# 03_MCU.net
KiCad netlist of a schematic drawn in Altium Designer
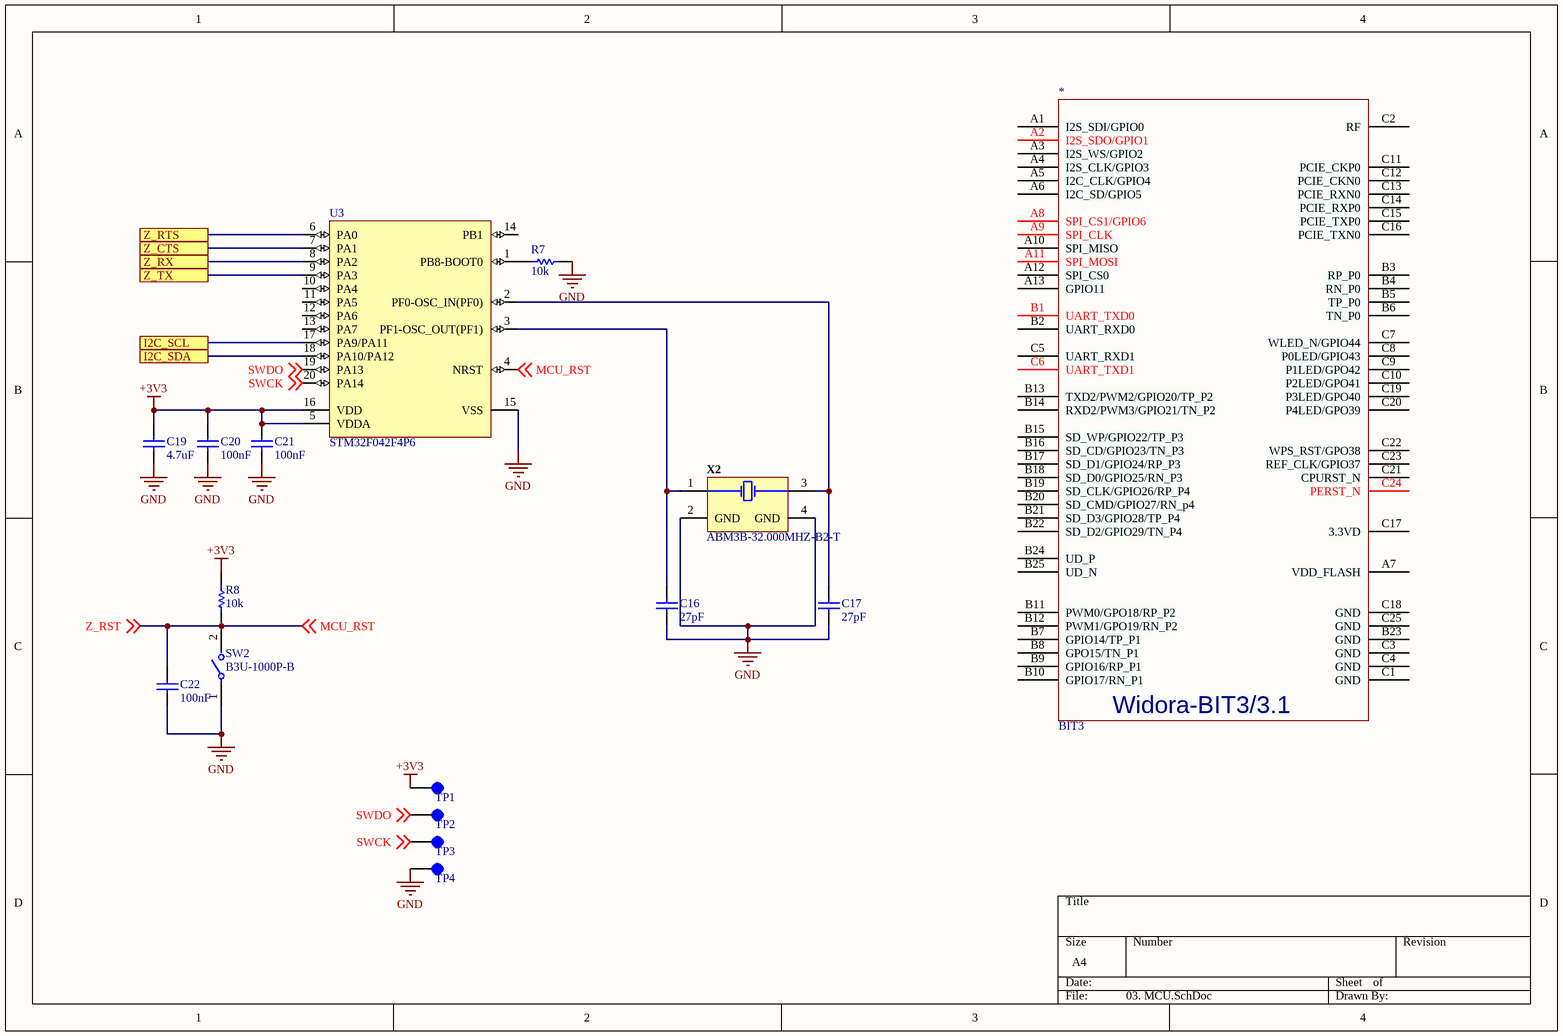
[diagram p0: 03. MCU.SchDoc]

(export (version "E")
  (design (tool "Eeschema 10.0.6"))
  (components
    (comp (ref "*") (value "BIT3") (footprint "Widora-BIT3") (libsource (lib "SyTungNguyen") (part "BIT3")))
    (comp (ref "C16")
      (value "27pF")
      (footprint "CAPC1005X56X25NL10T15")
      (fields
        (field (name "PART NUMBER") "04025A270FAT2A")
        (field (name "MANUFACTURER") "AVX Interconnect / Elco")
      )
      (libsource (lib "Altium Content Vault") (part "CAP"))
    )
    (comp (ref "C17")
      (value "27pF")
      (footprint "CAPC1005X56X25NL10T15")
      (fields
        (field (name "PART NUMBER") "04025A270FAT2A")
        (field (name "MANUFACTURER") "AVX Interconnect / Elco")
      )
      (libsource (lib "Altium Content Vault") (part "CAP"))
    )
    (comp (ref "C19")
      (value "4.7uF")
      (footprint "CAPC1608X90X35NL10T15")
      (fields (field (name "PART NUMBER") "GRM188R6YA475KE15D") (field (name "MANUFACTURER") "Murata"))
      (libsource (lib "Altium Content Vault") (part "CAP"))
    )
    (comp (ref "C20")
      (value "100nF")
      (footprint "CAPC1005X56X25NL10T15")
      (fields
        (field (name "MANUFACTURER") "AVX Interconnect / Elco")
        (field (name "PART NUMBER") "04026D104KAT2A")
      )
      (libsource (lib "Altium Content Vault") (part "CAP"))
    )
    (comp (ref "C21")
      (value "100nF")
      (footprint "CAPC1005X56X25NL10T15")
      (fields
        (field (name "MANUFACTURER") "AVX Interconnect / Elco")
        (field (name "PART NUMBER") "04026D104KAT2A")
      )
      (libsource (lib "Altium Content Vault") (part "CAP"))
    )
    (comp (ref "C22")
      (value "100nF")
      (footprint "CAPC1005X56X25NL10T15")
      (fields
        (field (name "MANUFACTURER") "AVX Interconnect / Elco")
        (field (name "PART NUMBER") "04026D104KAT2A")
      )
      (libsource (lib "Altium Content Vault") (part "CAP"))
    )
    (comp (ref "R7")
      (value "10k")
      (footprint "RESC1005X40X25NL05T05")
      (description "Chip Resistor, 10 KOhm, +/- 1%, 0.1 W, -55 to 155 degC, 0402 (1005 Metric), RoHS, Tape and Reel")
      (fields (field (name "TOLERANCE") "1%") (field (name "MANUFACTURER") "Panasonic"))
      (libsource (lib "Altium Content Vault") (part "RES-2"))
    )
    (comp (ref "R8")
      (value "10k")
      (footprint "RESC1005X40X25NL05T05")
      (description "Chip Resistor, 10 KOhm, +/- 1%, 0.1 W, -55 to 155 degC, 0402 (1005 Metric), RoHS, Tape and Reel")
      (fields (field (name "TOLERANCE") "1%") (field (name "MANUFACTURER") "Panasonic"))
      (libsource (lib "Altium Content Vault") (part "RES-2"))
    )
    (comp (ref "SW2")
      (value "B3U-1000P-B")
      (footprint "FP-B3U-1000P-B-MFG")
      (description "SWITCH TACTILE SPST-NO 0.05A 12V")
      (fields
        (field (name "OCTOPART") "https://octopart.com/b3u-1000p-b-omron-1057356")
        (field (name "MANUFACTURER") "Omron")
      )
      (libsource (lib "Altium Content Vault") (part "bb27bde45df87f1f469753f287ef5ae"))
    )
    (comp (ref "TP1") (value "Test Point") (footprint "TP") (libsource (lib "SyTungNguyen") (part "TP")))
    (comp (ref "TP2") (value "Test Point") (footprint "TP") (libsource (lib "SyTungNguyen") (part "TP")))
    (comp (ref "TP3") (value "Test Point") (footprint "TP") (libsource (lib "SyTungNguyen") (part "TP")))
    (comp (ref "TP4") (value "Test Point") (footprint "TP") (libsource (lib "SyTungNguyen") (part "TP")))
    (comp (ref "U3")
      (value "STM32F042F4P6")
      (footprint "STM-TSSOP20_M")
      (fields (field (name "MANUFACTURER") "STMicroelectronics"))
      (libsource (lib "Altium Content Vault") (part "MC-ARM-STM32F042-TSSOP20"))
    )
    (comp (ref "X2")
      (value "ABM3B-32.000MHZ-B2-T")
      (footprint "ABRA-ABM3B_V")
      (description "Ceramic SMD Crystal, 8 MHz, +/- 20 ppm, 200 Ohm, -20 to 70 degC, 4-Pin SMD, RoHS, Tape and Reel")
      (libsource (lib "Altium Content Vault") (part "XTAL-1-3-4"))
    )
  )
  (nets
    (net (code "1") (name "+3V3") (class "Default")
      (node (ref "C19") (pin "2") (pinfunction "2_2") (pintype "passive"))
      (node (ref "C20") (pin "2") (pinfunction "2_2") (pintype "passive"))
      (node (ref "C21") (pin "2") (pinfunction "2_2") (pintype "passive"))
      (node (ref "R8") (pin "1") (pinfunction "1_1") (pintype "passive"))
      (node (ref "TP1") (pin "1") (pintype "passive"))
      (node (ref "U3") (pin "16") (pinfunction "VDD_16") (pintype "power_in"))
      (node (ref "U3") (pin "5") (pinfunction "VDDA_5") (pintype "power_in"))
    )
    (net (code "2") (name "/I2C_SCL") (class "Default")
      (node (ref "U3") (pin "17") (pinfunction "PA9/PA11_17") (pintype "bidirectional"))
    )
    (net (code "3") (name "/I2C_SDA") (class "Default")
      (node (ref "U3") (pin "18") (pinfunction "PA10/PA12_18") (pintype "bidirectional"))
    )
    (net (code "4") (name "/Z_CTS") (class "Default")
      (node (ref "U3") (pin "7") (pinfunction "PA1_7") (pintype "bidirectional"))
    )
    (net (code "5") (name "/Z_RTS") (class "Default")
      (node (ref "U3") (pin "6") (pinfunction "PA0_6") (pintype "bidirectional"))
    )
    (net (code "6") (name "/Z_RX") (class "Default")
      (node (ref "U3") (pin "8") (pinfunction "PA2_8") (pintype "bidirectional"))
    )
    (net (code "7") (name "/Z_TX") (class "Default")
      (node (ref "U3") (pin "9") (pinfunction "PA3_9") (pintype "bidirectional"))
    )
    (net (code "8") (name "GND") (class "Default")
      (node (ref "C16") (pin "1") (pinfunction "1_1") (pintype "passive"))
      (node (ref "C17") (pin "1") (pinfunction "1_1") (pintype "passive"))
      (node (ref "C19") (pin "1") (pinfunction "1_1") (pintype "passive"))
      (node (ref "C20") (pin "1") (pinfunction "1_1") (pintype "passive"))
      (node (ref "C21") (pin "1") (pinfunction "1_1") (pintype "passive"))
      (node (ref "C22") (pin "1") (pinfunction "1_1") (pintype "passive"))
      (node (ref "R7") (pin "1") (pinfunction "1_1") (pintype "passive"))
      (node (ref "SW2") (pin "1") (pinfunction "1_1") (pintype "passive"))
      (node (ref "TP4") (pin "1") (pintype "passive"))
      (node (ref "U3") (pin "15") (pinfunction "VSS_15") (pintype "power_in"))
      (node (ref "X2") (pin "2") (pinfunction "GND_2") (pintype "power_in"))
      (node (ref "X2") (pin "4") (pinfunction "GND_4") (pintype "power_in"))
    )
    (net (code "9") (name "MCU_RST") (class "Default")
      (node (ref "C22") (pin "2") (pinfunction "2_2") (pintype "passive"))
      (node (ref "R8") (pin "2") (pinfunction "2_2") (pintype "passive"))
      (node (ref "SW2") (pin "2") (pinfunction "2_2") (pintype "passive"))
      (node (ref "U3") (pin "4") (pinfunction "NRST_4") (pintype "bidirectional"))
    )
    (net (code "10") (name "Net-(U3-PB8-BOOT0)") (class "Default")
      (node (ref "R7") (pin "2") (pinfunction "2_2") (pintype "passive"))
      (node (ref "U3") (pin "1") (pinfunction "PB8-BOOT0_1") (pintype "bidirectional"))
    )
    (net (code "11") (name "Net-(U3-PF0-OSC_IN(PF0))") (class "Default")
      (node (ref "C17") (pin "2") (pinfunction "2_2") (pintype "passive"))
      (node (ref "U3") (pin "2") (pinfunction "PF0-OSC_IN(PF0)_2") (pintype "bidirectional"))
      (node (ref "X2") (pin "3") (pinfunction "X2_3") (pintype "passive"))
    )
    (net (code "12") (name "Net-(U3-PF1-OSC_OUT(PF1))") (class "Default")
      (node (ref "C16") (pin "2") (pinfunction "2_2") (pintype "passive"))
      (node (ref "U3") (pin "3") (pinfunction "PF1-OSC_OUT(PF1)_3") (pintype "bidirectional"))
      (node (ref "X2") (pin "1") (pinfunction "X1_1") (pintype "passive"))
    )
    (net (code "13") (name "SWCK") (class "Default")
      (node (ref "TP3") (pin "1") (pintype "passive"))
      (node (ref "U3") (pin "20") (pinfunction "PA14_20") (pintype "bidirectional"))
    )
    (net (code "14") (name "SWDO") (class "Default")
      (node (ref "TP2") (pin "1") (pintype "passive"))
      (node (ref "U3") (pin "19") (pinfunction "PA13_19") (pintype "bidirectional"))
    )
    (net (code "15") (name "unconnected-(*-3.3VD-PadC17)") (class "Default")
      (node (ref "*") (pin "C17") (pinfunction "3.3VD_C17") (pintype "passive"))
    )
    (net (code "16") (name "unconnected-(*-CPURST_N-PadC21)") (class "Default")
      (node (ref "*") (pin "C21") (pinfunction "CPURST_N_C21") (pintype "passive"))
    )
    (net (code "17") (name "unconnected-(*-GND-PadB23)") (class "Default")
      (node (ref "*") (pin "B23") (pinfunction "GND_B23") (pintype "passive"))
    )
    (net (code "18") (name "unconnected-(*-GND-PadC1)") (class "Default")
      (node (ref "*") (pin "C1") (pinfunction "GND_C1") (pintype "passive"))
    )
    (net (code "19") (name "unconnected-(*-GND-PadC3)") (class "Default")
      (node (ref "*") (pin "C3") (pinfunction "GND_C3") (pintype "passive"))
    )
    (net (code "20") (name "unconnected-(*-GND-PadC4)") (class "Default")
      (node (ref "*") (pin "C4") (pinfunction "GND_C4") (pintype "passive"))
    )
    (net (code "21") (name "unconnected-(*-GND-PadC18)") (class "Default")
      (node (ref "*") (pin "C18") (pinfunction "GND_C18") (pintype "passive"))
    )
    (net (code "22") (name "unconnected-(*-GND-PadC25)") (class "Default")
      (node (ref "*") (pin "C25") (pinfunction "GND_C25") (pintype "passive"))
    )
    (net (code "23") (name "unconnected-(*-GPIO11-PadA13)") (class "Default")
      (node (ref "*") (pin "A13") (pinfunction "GPIO11_A13") (pintype "passive"))
    )
    (net (code "24") (name "unconnected-(*-GPIO14{slash}TP_P1-PadB7)") (class "Default")
      (node (ref "*") (pin "B7") (pinfunction "GPIO14/TP_P1_B7") (pintype "passive"))
    )
    (net (code "25") (name "unconnected-(*-GPIO16{slash}RP_P1-PadB9)") (class "Default")
      (node (ref "*") (pin "B9") (pinfunction "GPIO16/RP_P1_B9") (pintype "passive"))
    )
    (net (code "26") (name "unconnected-(*-GPIO17{slash}RN_P1-PadB10)") (class "Default")
      (node (ref "*") (pin "B10") (pinfunction "GPIO17/RN_P1_B10") (pintype "passive"))
    )
    (net (code "27") (name "unconnected-(*-GPO15{slash}TN_P1-PadB8)") (class "Default")
      (node (ref "*") (pin "B8") (pinfunction "GPO15/TN_P1_B8") (pintype "passive"))
    )
    (net (code "28") (name "unconnected-(*-I2C_CLK{slash}GPIO4-PadA5)") (class "Default")
      (node (ref "*") (pin "A5") (pinfunction "I2C_CLK/GPIO4_A5") (pintype "passive"))
    )
    (net (code "29") (name "unconnected-(*-I2C_SD{slash}GPIO5-PadA6)") (class "Default")
      (node (ref "*") (pin "A6") (pinfunction "I2C_SD/GPIO5_A6") (pintype "passive"))
    )
    (net (code "30") (name "unconnected-(*-I2S_CLK{slash}GPIO3-PadA4)") (class "Default")
      (node (ref "*") (pin "A4") (pinfunction "I2S_CLK/GPIO3_A4") (pintype "passive"))
    )
    (net (code "31") (name "unconnected-(*-I2S_SDI{slash}GPIO0-PadA1)") (class "Default")
      (node (ref "*") (pin "A1") (pinfunction "I2S_SDI/GPIO0_A1") (pintype "passive"))
    )
    (net (code "32") (name "unconnected-(*-I2S_SDO{slash}GPIO1-PadA2)") (class "Default")
      (node (ref "*") (pin "A2") (pinfunction "I2S_SDO/GPIO1_A2") (pintype "passive"))
    )
    (net (code "33") (name "unconnected-(*-I2S_WS{slash}GPIO2-PadA3)") (class "Default")
      (node (ref "*") (pin "A3") (pinfunction "I2S_WS/GPIO2_A3") (pintype "passive"))
    )
    (net (code "34") (name "unconnected-(*-P0LED{slash}GPIO43-PadC8)") (class "Default")
      (node (ref "*") (pin "C8") (pinfunction "P0LED/GPIO43_C8") (pintype "passive"))
    )
    (net (code "35") (name "unconnected-(*-P1LED{slash}GPO42-PadC9)") (class "Default")
      (node (ref "*") (pin "C9") (pinfunction "P1LED/GPO42_C9") (pintype "passive"))
    )
    (net (code "36") (name "unconnected-(*-P2LED{slash}GPO41-PadC10)") (class "Default")
      (node (ref "*") (pin "C10") (pinfunction "P2LED/GPO41_C10") (pintype "passive"))
    )
    (net (code "37") (name "unconnected-(*-P3LED{slash}GPO40-PadC19)") (class "Default")
      (node (ref "*") (pin "C19") (pinfunction "P3LED/GPO40_C19") (pintype "passive"))
    )
    (net (code "38") (name "unconnected-(*-P4LED{slash}GPO39-PadC20)") (class "Default")
      (node (ref "*") (pin "C20") (pinfunction "P4LED/GPO39_C20") (pintype "passive"))
    )
    (net (code "39") (name "unconnected-(*-PCIE_CKN0-PadC12)") (class "Default")
      (node (ref "*") (pin "C12") (pinfunction "PCIE_CKN0_C12") (pintype "passive"))
    )
    (net (code "40") (name "unconnected-(*-PCIE_CKP0-PadC11)") (class "Default")
      (node (ref "*") (pin "C11") (pinfunction "PCIE_CKP0_C11") (pintype "passive"))
    )
    (net (code "41") (name "unconnected-(*-PCIE_RXN0-PadC13)") (class "Default")
      (node (ref "*") (pin "C13") (pinfunction "PCIE_RXN0_C13") (pintype "passive"))
    )
    (net (code "42") (name "unconnected-(*-PCIE_RXP0-PadC14)") (class "Default")
      (node (ref "*") (pin "C14") (pinfunction "PCIE_RXP0_C14") (pintype "passive"))
    )
    (net (code "43") (name "unconnected-(*-PCIE_TXN0-PadC16)") (class "Default")
      (node (ref "*") (pin "C16") (pinfunction "PCIE_TXN0_C16") (pintype "passive"))
    )
    (net (code "44") (name "unconnected-(*-PCIE_TXP0-PadC15)") (class "Default")
      (node (ref "*") (pin "C15") (pinfunction "PCIE_TXP0_C15") (pintype "passive"))
    )
    (net (code "45") (name "unconnected-(*-PERST_N-PadC24)") (class "Default")
      (node (ref "*") (pin "C24") (pinfunction "PERST_N_C24") (pintype "passive"))
    )
    (net (code "46") (name "unconnected-(*-PWM0{slash}GPO18{slash}RP_P2-PadB11)") (class "Default")
      (node (ref "*") (pin "B11") (pinfunction "PWM0/GPO18/RP_P2_B11") (pintype "passive"))
    )
    (net (code "47") (name "unconnected-(*-PWM1{slash}GPO19{slash}RN_P2-PadB12)") (class "Default")
      (node (ref "*") (pin "B12") (pinfunction "PWM1/GPO19/RN_P2_B12") (pintype "passive"))
    )
    (net (code "48") (name "unconnected-(*-REF_CLK{slash}GPIO37-PadC23)") (class "Default")
      (node (ref "*") (pin "C23") (pinfunction "REF_CLK/GPIO37_C23") (pintype "passive"))
    )
    (net (code "49") (name "unconnected-(*-RF-PadC2)") (class "Default")
      (node (ref "*") (pin "C2") (pinfunction "RF_C2") (pintype "passive"))
    )
    (net (code "50") (name "unconnected-(*-RN_P0-PadB4)") (class "Default")
      (node (ref "*") (pin "B4") (pinfunction "RN_P0_B4") (pintype "passive"))
    )
    (net (code "51") (name "unconnected-(*-RP_P0-PadB3)") (class "Default")
      (node (ref "*") (pin "B3") (pinfunction "RP_P0_B3") (pintype "passive"))
    )
    (net (code "52") (name "unconnected-(*-RXD2{slash}PWM3{slash}GPIO21{slash}TN_P2-PadB14)") (class "Default")
      (node (ref "*") (pin "B14") (pinfunction "RXD2/PWM3/GPIO21/TN_P2_B14") (pintype "passive"))
    )
    (net (code "53") (name "unconnected-(*-SD_CD{slash}GPIO23{slash}TN_P3-PadB16)") (class "Default")
      (node (ref "*") (pin "B16") (pinfunction "SD_CD/GPIO23/TN_P3_B16") (pintype "passive"))
    )
    (net (code "54") (name "unconnected-(*-SD_CLK{slash}GPIO26{slash}RP_P4-PadB19)") (class "Default")
      (node (ref "*") (pin "B19") (pinfunction "SD_CLK/GPIO26/RP_P4_B19") (pintype "passive"))
    )
    (net (code "55") (name "unconnected-(*-SD_CMD{slash}GPIO27{slash}RN_p4-PadB20)") (class "Default")
      (node (ref "*") (pin "B20") (pinfunction "SD_CMD/GPIO27/RN_p4_B20") (pintype "passive"))
    )
    (net (code "56") (name "unconnected-(*-SD_D0{slash}GPIO25{slash}RN_P3-PadB18)") (class "Default")
      (node (ref "*") (pin "B18") (pinfunction "SD_D0/GPIO25/RN_P3_B18") (pintype "passive"))
    )
    (net (code "57") (name "unconnected-(*-SD_D1{slash}GPIO24{slash}RP_P3-PadB17)") (class "Default")
      (node (ref "*") (pin "B17") (pinfunction "SD_D1/GPIO24/RP_P3_B17") (pintype "passive"))
    )
    (net (code "58") (name "unconnected-(*-SD_D2{slash}GPIO29{slash}TN_P4-PadB22)") (class "Default")
      (node (ref "*") (pin "B22") (pinfunction "SD_D2/GPIO29/TN_P4_B22") (pintype "passive"))
    )
    (net (code "59") (name "unconnected-(*-SD_D3{slash}GPIO28{slash}TP_P4-PadB21)") (class "Default")
      (node (ref "*") (pin "B21") (pinfunction "SD_D3/GPIO28/TP_P4_B21") (pintype "passive"))
    )
    (net (code "60") (name "unconnected-(*-SD_WP{slash}GPIO22{slash}TP_P3-PadB15)") (class "Default")
      (node (ref "*") (pin "B15") (pinfunction "SD_WP/GPIO22/TP_P3_B15") (pintype "passive"))
    )
    (net (code "61") (name "unconnected-(*-SPI_CLK-PadA9)") (class "Default")
      (node (ref "*") (pin "A9") (pinfunction "SPI_CLK_A9") (pintype "passive"))
    )
    (net (code "62") (name "unconnected-(*-SPI_CS0-PadA12)") (class "Default")
      (node (ref "*") (pin "A12") (pinfunction "SPI_CS0_A12") (pintype "passive"))
    )
    (net (code "63") (name "unconnected-(*-SPI_CS1{slash}GPIO6-PadA8)") (class "Default")
      (node (ref "*") (pin "A8") (pinfunction "SPI_CS1/GPIO6_A8") (pintype "passive"))
    )
    (net (code "64") (name "unconnected-(*-SPI_MISO-PadA10)") (class "Default")
      (node (ref "*") (pin "A10") (pinfunction "SPI_MISO_A10") (pintype "passive"))
    )
    (net (code "65") (name "unconnected-(*-SPI_MOSI-PadA11)") (class "Default")
      (node (ref "*") (pin "A11") (pinfunction "SPI_MOSI_A11") (pintype "passive"))
    )
    (net (code "66") (name "unconnected-(*-TN_P0-PadB6)") (class "Default")
      (node (ref "*") (pin "B6") (pinfunction "TN_P0_B6") (pintype "passive"))
    )
    (net (code "67") (name "unconnected-(*-TP_P0-PadB5)") (class "Default")
      (node (ref "*") (pin "B5") (pinfunction "TP_P0_B5") (pintype "passive"))
    )
    (net (code "68") (name "unconnected-(*-TXD2{slash}PWM2{slash}GPIO20{slash}TP_P2-PadB13)") (class "Default")
      (node (ref "*") (pin "B13") (pinfunction "TXD2/PWM2/GPIO20/TP_P2_B13") (pintype "passive"))
    )
    (net (code "69") (name "unconnected-(*-UART_RXD0-PadB2)") (class "Default")
      (node (ref "*") (pin "B2") (pinfunction "UART_RXD0_B2") (pintype "passive"))
    )
    (net (code "70") (name "unconnected-(*-UART_RXD1-PadC5)") (class "Default")
      (node (ref "*") (pin "C5") (pinfunction "UART_RXD1_C5") (pintype "passive"))
    )
    (net (code "71") (name "unconnected-(*-UART_TXD0-PadB1)") (class "Default")
      (node (ref "*") (pin "B1") (pinfunction "UART_TXD0_B1") (pintype "passive"))
    )
    (net (code "72") (name "unconnected-(*-UART_TXD1-PadC6)") (class "Default")
      (node (ref "*") (pin "C6") (pinfunction "UART_TXD1_C6") (pintype "passive"))
    )
    (net (code "73") (name "unconnected-(*-UD_N-PadB25)") (class "Default")
      (node (ref "*") (pin "B25") (pinfunction "UD_N_B25") (pintype "passive"))
    )
    (net (code "74") (name "unconnected-(*-UD_P-PadB24)") (class "Default")
      (node (ref "*") (pin "B24") (pinfunction "UD_P_B24") (pintype "passive"))
    )
    (net (code "75") (name "unconnected-(*-VDD_FLASH-PadA7)") (class "Default")
      (node (ref "*") (pin "A7") (pinfunction "VDD_FLASH_A7") (pintype "passive"))
    )
    (net (code "76") (name "unconnected-(*-WLED_N{slash}GPIO44-PadC7)") (class "Default")
      (node (ref "*") (pin "C7") (pinfunction "WLED_N/GPIO44_C7") (pintype "passive"))
    )
    (net (code "77") (name "unconnected-(*-WPS_RST{slash}GPO38-PadC22)") (class "Default")
      (node (ref "*") (pin "C22") (pinfunction "WPS_RST/GPO38_C22") (pintype "passive"))
    )
    (net (code "78") (name "unconnected-(U3-PA4-Pad10)") (class "Default")
      (node (ref "U3") (pin "10") (pinfunction "PA4_10") (pintype "bidirectional"))
    )
    (net (code "79") (name "unconnected-(U3-PA5-Pad11)") (class "Default")
      (node (ref "U3") (pin "11") (pinfunction "PA5_11") (pintype "bidirectional"))
    )
    (net (code "80") (name "unconnected-(U3-PA6-Pad12)") (class "Default")
      (node (ref "U3") (pin "12") (pinfunction "PA6_12") (pintype "bidirectional"))
    )
    (net (code "81") (name "unconnected-(U3-PA7-Pad13)") (class "Default")
      (node (ref "U3") (pin "13") (pinfunction "PA7_13") (pintype "bidirectional"))
    )
    (net (code "82") (name "unconnected-(U3-PB1-Pad14)") (class "Default")
      (node (ref "U3") (pin "14") (pinfunction "PB1_14") (pintype "bidirectional"))
    )
  )
)
